# Amiga_500_ROM_Adapter_Rev1.net
KiCad netlist of a schematic drawn in EAGLE
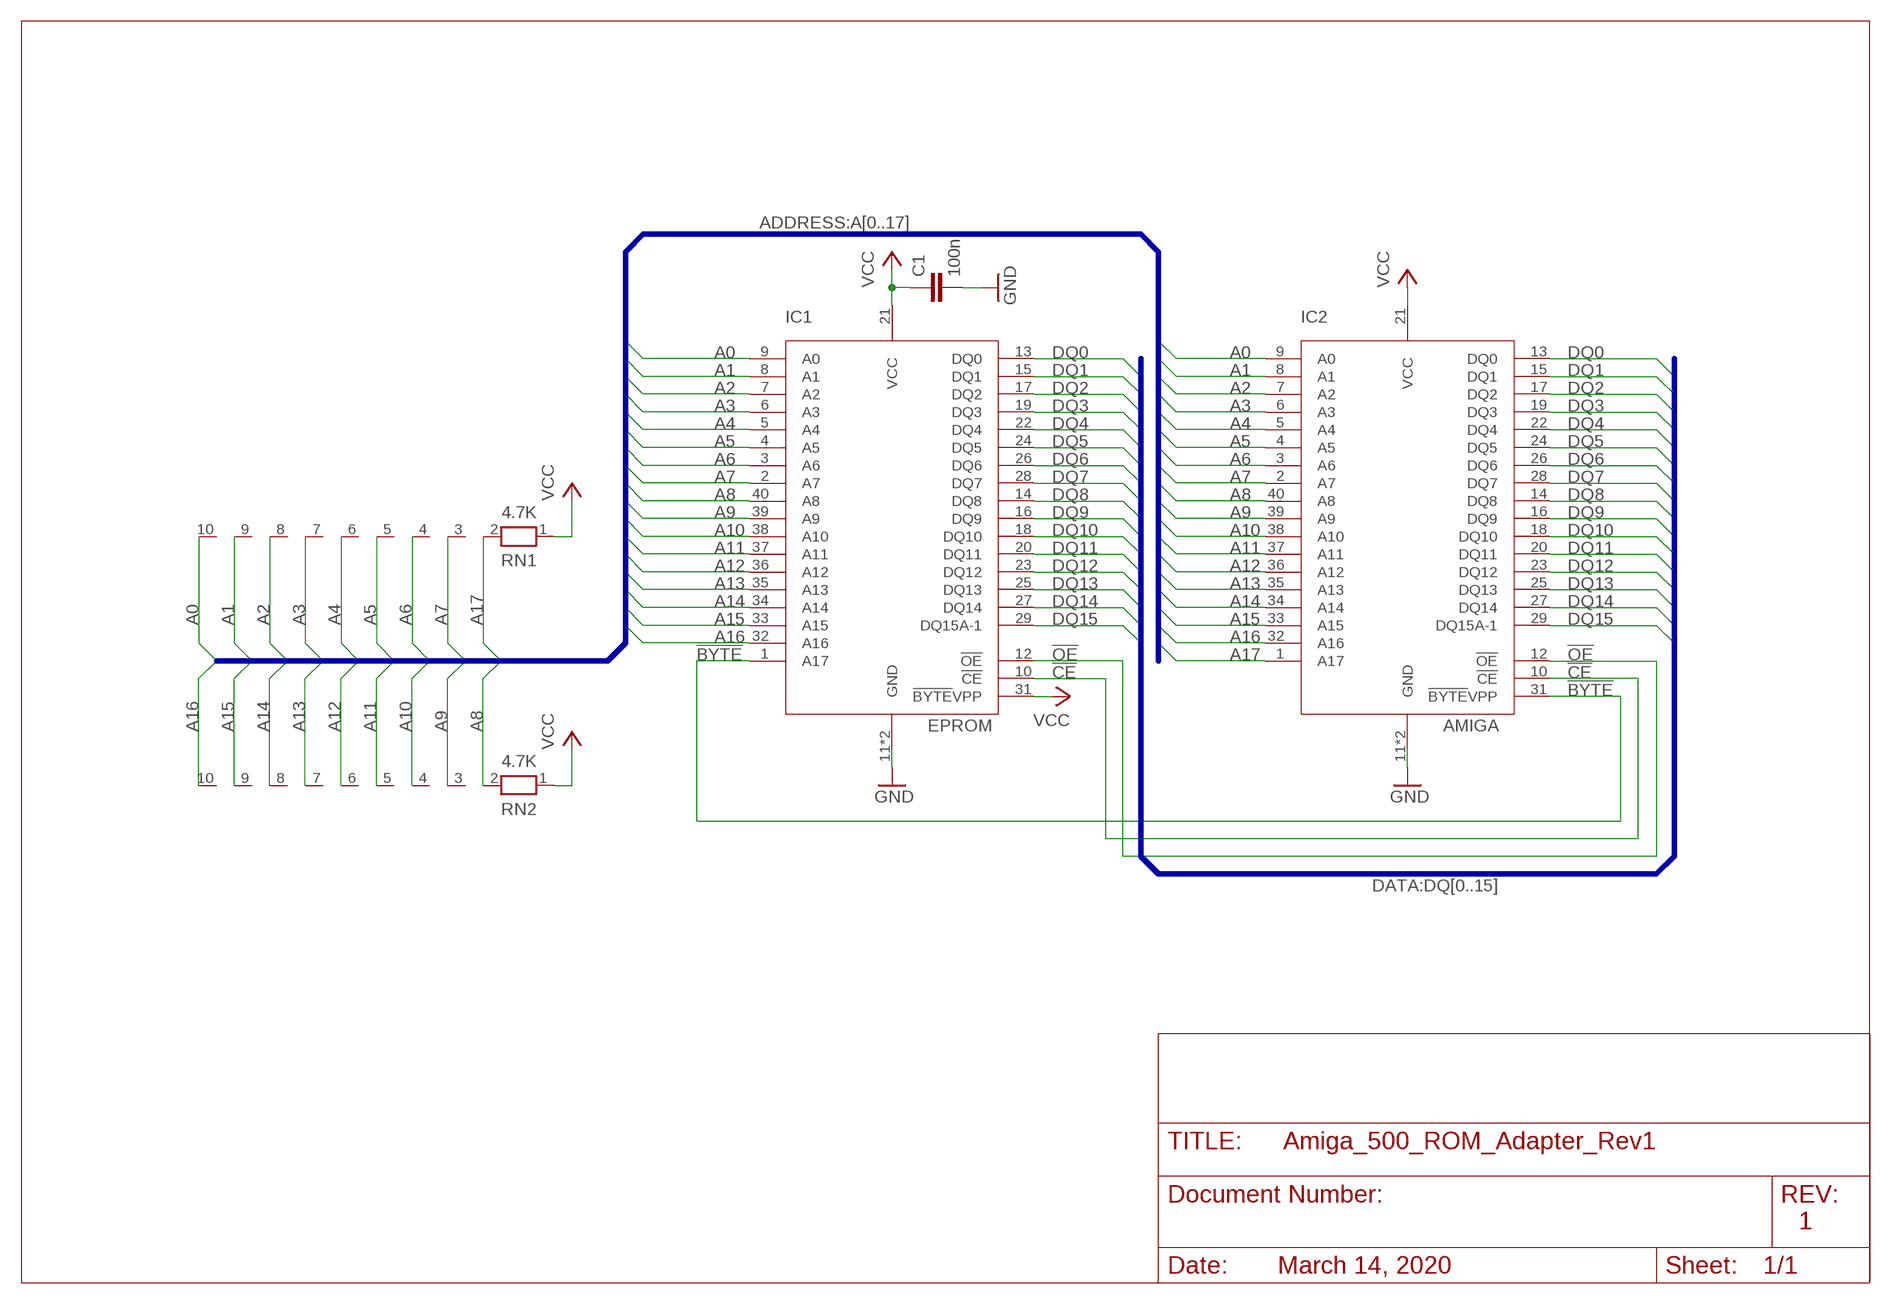
[diagram p0: schematic, sheet 1]

(export (version "E")
  (design (tool "Eeschema 10.0.6"))
  (components
    (comp (ref "C1")
      (value "100n")
      (footprint "eagle-import:C025-025X050")
      (libsource (lib "eagle-import") (part "C-EU025-025X050"))
    )
    (comp (ref "IC1")
      (value "EPROM")
      (footprint "eagle-import:DIL40-6")
      (libsource (lib "eagle-import") (part "27C400"))
    )
    (comp (ref "IC2")
      (value "AMIGA")
      (footprint "eagle-import:DIL40-6")
      (libsource (lib "eagle-import") (part "27C400"))
    )
    (comp (ref "RN1")
      (value "4.7K")
      (footprint "eagle-import:RN-10")
      (libsource (lib "eagle-import") (part "RN09"))
    )
    (comp (ref "RN2")
      (value "4.7K")
      (footprint "eagle-import:RN-10")
      (libsource (lib "eagle-import") (part "RN09"))
    )
  )
  (nets
    (net (code "35") (name "/A0") (class "Default")
      (node (ref "IC1") (pin "9") (pinfunction "A0_9") (pintype "bidirectional"))
      (node (ref "IC2") (pin "9") (pinfunction "A0_9") (pintype "bidirectional"))
      (node (ref "RN1") (pin "10") (pinfunction "10_10") (pintype "passive"))
    )
    (net (code "36") (name "/A1") (class "Default")
      (node (ref "IC1") (pin "8") (pinfunction "A1_8") (pintype "bidirectional"))
      (node (ref "IC2") (pin "8") (pinfunction "A1_8") (pintype "bidirectional"))
      (node (ref "RN1") (pin "9") (pinfunction "9_9") (pintype "passive"))
    )
    (net (code "37") (name "/A2") (class "Default")
      (node (ref "IC1") (pin "7") (pinfunction "A2_7") (pintype "bidirectional"))
      (node (ref "IC2") (pin "7") (pinfunction "A2_7") (pintype "bidirectional"))
      (node (ref "RN1") (pin "8") (pinfunction "8_8") (pintype "passive"))
    )
    (net (code "38") (name "/A3") (class "Default")
      (node (ref "IC1") (pin "6") (pinfunction "A3_6") (pintype "bidirectional"))
      (node (ref "IC2") (pin "6") (pinfunction "A3_6") (pintype "bidirectional"))
      (node (ref "RN1") (pin "7") (pinfunction "7_7") (pintype "passive"))
    )
    (net (code "39") (name "/A4") (class "Default")
      (node (ref "IC1") (pin "5") (pinfunction "A4_5") (pintype "bidirectional"))
      (node (ref "IC2") (pin "5") (pinfunction "A4_5") (pintype "bidirectional"))
      (node (ref "RN1") (pin "6") (pinfunction "6_6") (pintype "passive"))
    )
    (net (code "40") (name "/A5") (class "Default")
      (node (ref "IC1") (pin "4") (pinfunction "A5_4") (pintype "bidirectional"))
      (node (ref "IC2") (pin "4") (pinfunction "A5_4") (pintype "bidirectional"))
      (node (ref "RN1") (pin "5") (pinfunction "5_5") (pintype "passive"))
    )
    (net (code "41") (name "/A6") (class "Default")
      (node (ref "IC1") (pin "3") (pinfunction "A6_3") (pintype "bidirectional"))
      (node (ref "IC2") (pin "3") (pinfunction "A6_3") (pintype "bidirectional"))
      (node (ref "RN1") (pin "4") (pinfunction "4_4") (pintype "passive"))
    )
    (net (code "42") (name "/A7") (class "Default")
      (node (ref "IC1") (pin "2") (pinfunction "A7_2") (pintype "bidirectional"))
      (node (ref "IC2") (pin "2") (pinfunction "A7_2") (pintype "bidirectional"))
      (node (ref "RN1") (pin "3") (pinfunction "3_3") (pintype "passive"))
    )
    (net (code "43") (name "/A8") (class "Default")
      (node (ref "IC1") (pin "40") (pinfunction "A8_40") (pintype "bidirectional"))
      (node (ref "IC2") (pin "40") (pinfunction "A8_40") (pintype "bidirectional"))
      (node (ref "RN2") (pin "2") (pinfunction "2_2") (pintype "passive"))
    )
    (net (code "44") (name "/A9") (class "Default")
      (node (ref "IC1") (pin "39") (pinfunction "A9_39") (pintype "bidirectional"))
      (node (ref "IC2") (pin "39") (pinfunction "A9_39") (pintype "bidirectional"))
      (node (ref "RN2") (pin "3") (pinfunction "3_3") (pintype "passive"))
    )
    (net (code "45") (name "/A10") (class "Default")
      (node (ref "IC1") (pin "38") (pinfunction "A10_38") (pintype "bidirectional"))
      (node (ref "IC2") (pin "38") (pinfunction "A10_38") (pintype "bidirectional"))
      (node (ref "RN2") (pin "4") (pinfunction "4_4") (pintype "passive"))
    )
    (net (code "46") (name "/A11") (class "Default")
      (node (ref "IC1") (pin "37") (pinfunction "A11_37") (pintype "bidirectional"))
      (node (ref "IC2") (pin "37") (pinfunction "A11_37") (pintype "bidirectional"))
      (node (ref "RN2") (pin "5") (pinfunction "5_5") (pintype "passive"))
    )
    (net (code "47") (name "/A12") (class "Default")
      (node (ref "IC1") (pin "36") (pinfunction "A12_36") (pintype "bidirectional"))
      (node (ref "IC2") (pin "36") (pinfunction "A12_36") (pintype "bidirectional"))
      (node (ref "RN2") (pin "6") (pinfunction "6_6") (pintype "passive"))
    )
    (net (code "48") (name "/A13") (class "Default")
      (node (ref "IC1") (pin "35") (pinfunction "A13_35") (pintype "bidirectional"))
      (node (ref "IC2") (pin "35") (pinfunction "A13_35") (pintype "bidirectional"))
      (node (ref "RN2") (pin "7") (pinfunction "7_7") (pintype "passive"))
    )
    (net (code "49") (name "/A14") (class "Default")
      (node (ref "IC1") (pin "34") (pinfunction "A14_34") (pintype "bidirectional"))
      (node (ref "IC2") (pin "34") (pinfunction "A14_34") (pintype "bidirectional"))
      (node (ref "RN2") (pin "8") (pinfunction "8_8") (pintype "passive"))
    )
    (net (code "50") (name "/A15") (class "Default")
      (node (ref "IC1") (pin "33") (pinfunction "A15_33") (pintype "bidirectional"))
      (node (ref "IC2") (pin "33") (pinfunction "A15_33") (pintype "bidirectional"))
      (node (ref "RN2") (pin "9") (pinfunction "9_9") (pintype "passive"))
    )
    (net (code "51") (name "/A16") (class "Default")
      (node (ref "IC1") (pin "32") (pinfunction "A16_32") (pintype "bidirectional"))
      (node (ref "IC2") (pin "32") (pinfunction "A16_32") (pintype "bidirectional"))
      (node (ref "RN2") (pin "10") (pinfunction "10_10") (pintype "passive"))
    )
    (net (code "52") (name "/A17") (class "Default")
      (node (ref "IC2") (pin "1") (pinfunction "A17_1") (pintype "bidirectional"))
      (node (ref "RN1") (pin "2") (pinfunction "2_2") (pintype "passive"))
    )
    (net (code "55") (name "/DQ0") (class "Default")
      (node (ref "IC1") (pin "13") (pinfunction "DQ0_13") (pintype "bidirectional"))
      (node (ref "IC2") (pin "13") (pinfunction "DQ0_13") (pintype "bidirectional"))
    )
    (net (code "56") (name "/DQ1") (class "Default")
      (node (ref "IC1") (pin "15") (pinfunction "DQ1_15") (pintype "bidirectional"))
      (node (ref "IC2") (pin "15") (pinfunction "DQ1_15") (pintype "bidirectional"))
    )
    (net (code "57") (name "/DQ2") (class "Default")
      (node (ref "IC1") (pin "17") (pinfunction "DQ2_17") (pintype "bidirectional"))
      (node (ref "IC2") (pin "17") (pinfunction "DQ2_17") (pintype "bidirectional"))
    )
    (net (code "58") (name "/DQ3") (class "Default")
      (node (ref "IC1") (pin "19") (pinfunction "DQ3_19") (pintype "bidirectional"))
      (node (ref "IC2") (pin "19") (pinfunction "DQ3_19") (pintype "bidirectional"))
    )
    (net (code "59") (name "/DQ4") (class "Default")
      (node (ref "IC1") (pin "22") (pinfunction "DQ4_22") (pintype "bidirectional"))
      (node (ref "IC2") (pin "22") (pinfunction "DQ4_22") (pintype "bidirectional"))
    )
    (net (code "60") (name "/DQ5") (class "Default")
      (node (ref "IC1") (pin "24") (pinfunction "DQ5_24") (pintype "bidirectional"))
      (node (ref "IC2") (pin "24") (pinfunction "DQ5_24") (pintype "bidirectional"))
    )
    (net (code "61") (name "/DQ6") (class "Default")
      (node (ref "IC1") (pin "26") (pinfunction "DQ6_26") (pintype "bidirectional"))
      (node (ref "IC2") (pin "26") (pinfunction "DQ6_26") (pintype "bidirectional"))
    )
    (net (code "62") (name "/DQ7") (class "Default")
      (node (ref "IC1") (pin "28") (pinfunction "DQ7_28") (pintype "bidirectional"))
      (node (ref "IC2") (pin "28") (pinfunction "DQ7_28") (pintype "bidirectional"))
    )
    (net (code "63") (name "/DQ8") (class "Default")
      (node (ref "IC1") (pin "14") (pinfunction "DQ8_14") (pintype "bidirectional"))
      (node (ref "IC2") (pin "14") (pinfunction "DQ8_14") (pintype "bidirectional"))
    )
    (net (code "64") (name "/DQ9") (class "Default")
      (node (ref "IC1") (pin "16") (pinfunction "DQ9_16") (pintype "bidirectional"))
      (node (ref "IC2") (pin "16") (pinfunction "DQ9_16") (pintype "bidirectional"))
    )
    (net (code "65") (name "/DQ10") (class "Default")
      (node (ref "IC1") (pin "18") (pinfunction "DQ10_18") (pintype "bidirectional"))
      (node (ref "IC2") (pin "18") (pinfunction "DQ10_18") (pintype "bidirectional"))
    )
    (net (code "66") (name "/DQ11") (class "Default")
      (node (ref "IC1") (pin "20") (pinfunction "DQ11_20") (pintype "bidirectional"))
      (node (ref "IC2") (pin "20") (pinfunction "DQ11_20") (pintype "bidirectional"))
    )
    (net (code "67") (name "/DQ12") (class "Default")
      (node (ref "IC1") (pin "23") (pinfunction "DQ12_23") (pintype "bidirectional"))
      (node (ref "IC2") (pin "23") (pinfunction "DQ12_23") (pintype "bidirectional"))
    )
    (net (code "68") (name "/DQ13") (class "Default")
      (node (ref "IC1") (pin "25") (pinfunction "DQ13_25") (pintype "bidirectional"))
      (node (ref "IC2") (pin "25") (pinfunction "DQ13_25") (pintype "bidirectional"))
    )
    (net (code "69") (name "/DQ14") (class "Default")
      (node (ref "IC1") (pin "27") (pinfunction "DQ14_27") (pintype "bidirectional"))
      (node (ref "IC2") (pin "27") (pinfunction "DQ14_27") (pintype "bidirectional"))
    )
    (net (code "70") (name "/DQ15") (class "Default")
      (node (ref "IC1") (pin "29") (pinfunction "DQ15A-1_29") (pintype "bidirectional"))
      (node (ref "IC2") (pin "29") (pinfunction "DQ15A-1_29") (pintype "bidirectional"))
    )
    (net (code "71") (name "/~{BYTE}") (class "Default")
      (node (ref "IC1") (pin "1") (pinfunction "A17_1") (pintype "bidirectional"))
      (node (ref "IC2") (pin "31") (pinfunction "~{BYTE}VPP_31") (pintype "bidirectional"))
    )
    (net (code "72") (name "/~{CE}") (class "Default")
      (node (ref "IC1") (pin "10") (pinfunction "~{CE}_10") (pintype "bidirectional"))
      (node (ref "IC2") (pin "10") (pinfunction "~{CE}_10") (pintype "bidirectional"))
    )
    (net (code "73") (name "/~{OE}") (class "Default")
      (node (ref "IC1") (pin "12") (pinfunction "~{OE}_12") (pintype "bidirectional"))
      (node (ref "IC2") (pin "12") (pinfunction "~{OE}_12") (pintype "bidirectional"))
    )
    (net (code "74") (name "GND") (class "Default")
      (node (ref "C1") (pin "2") (pinfunction "2_2") (pintype "passive"))
      (node (ref "IC1") (pin "11") (pinfunction "GND_11") (pintype "power_in"))
      (node (ref "IC1") (pin "30") (pinfunction "GND_30") (pintype "power_in"))
      (node (ref "IC2") (pin "11") (pinfunction "GND_11") (pintype "power_in"))
      (node (ref "IC2") (pin "30") (pinfunction "GND_30") (pintype "power_in"))
    )
    (net (code "75") (name "VCC") (class "Default")
      (node (ref "C1") (pin "1") (pinfunction "1_1") (pintype "passive"))
      (node (ref "IC1") (pin "21") (pinfunction "VCC_21") (pintype "power_in"))
      (node (ref "IC1") (pin "31") (pinfunction "~{BYTE}VPP_31") (pintype "bidirectional"))
      (node (ref "IC2") (pin "21") (pinfunction "VCC_21") (pintype "power_in"))
      (node (ref "RN1") (pin "1") (pinfunction "1_1") (pintype "passive"))
      (node (ref "RN2") (pin "1") (pinfunction "1_1") (pintype "passive"))
    )
  )
)
